# Battery_Charger.net
KiCad netlist of a schematic drawn in Altium Designer
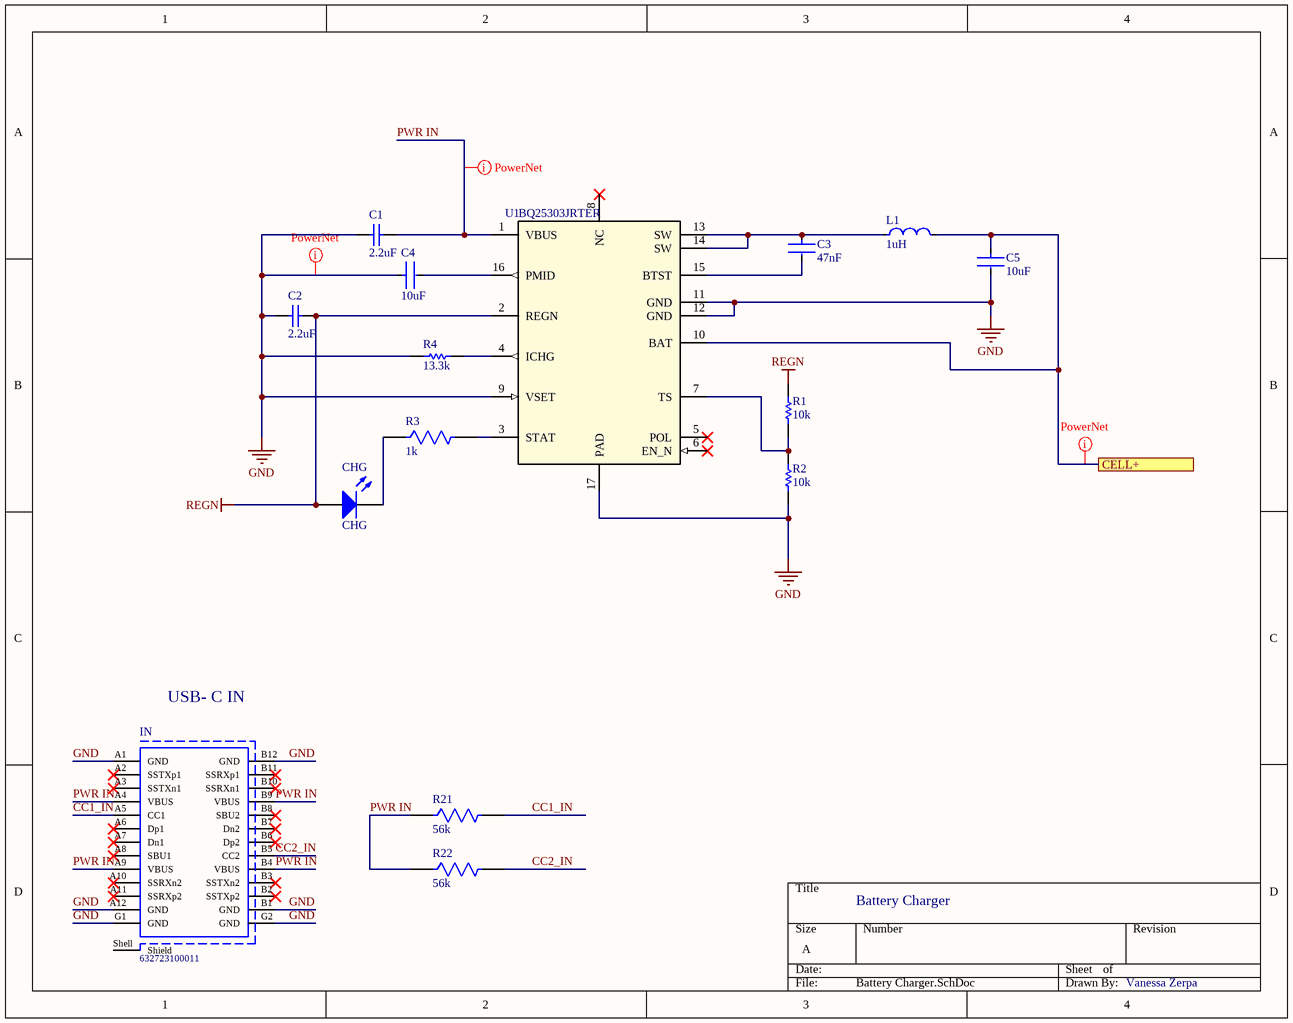
[diagram p0: Battery Charger.SchDoc]

(export (version "E")
  (design (tool "Eeschema 10.0.6"))
  (components
    (comp (ref "C1")
      (value "2.2uF")
      (footprint "CAPC2013X152X50ML20T25")
      (fields
        (field (name "PART NUMBER") "08053C225KAT2A")
        (field (name "MANUFACTURER") "AVX Interconnect / Elco")
      )
      (libsource (lib "Altium Content Vault") (part "CAP"))
    )
    (comp (ref "C2")
      (value "2.2uF")
      (footprint "CAPC2013X152X50ML20T25")
      (fields
        (field (name "PART NUMBER") "08053C225KAT2A")
        (field (name "MANUFACTURER") "AVX Interconnect / Elco")
      )
      (libsource (lib "Altium Content Vault") (part "CAP"))
    )
    (comp (ref "C3")
      (value "47nF")
      (footprint "FP-C0805C-DN-MFG")
      (description "CAP CER 0.047UF 25V 5% NP0 0805")
      (fields
        (field (name "MANUFACTURER PART NUMBER") "C0805C473J3GACTU")
        (field (name "OCTOPART") "https://octopart.com/c0805c473j3gactu-kemet-9563153")
      )
      (libsource (lib "Altium Content Vault") (part "b4654b650e69147ec39a6b967a45e02"))
    )
    (comp (ref "C4")
      (value "10uF")
      (footprint "FP-C0805C-DG-MFG")
      (description "CAP CER 10UF 10V X5R 0805")
      (fields (field (name "TOLERANCE") "10%") (field (name "MANUFACTURER PART NUMBER") "C0805C106K8PACTU"))
      (libsource (lib "Altium Content Vault") (part "11868f565c42a9108669ba33697ecf6"))
    )
    (comp (ref "C5")
      (value "10uF")
      (footprint "FP-C0805C-DG-MFG")
      (description "CAP CER 10UF 10V X5R 0805")
      (fields (field (name "TOLERANCE") "10%") (field (name "MANUFACTURER PART NUMBER") "C0805C106K8PACTU"))
      (libsource (lib "Altium Content Vault") (part "11868f565c42a9108669ba33697ecf6"))
    )
    (comp (ref "CHG")
      (value "CHG")
      (footprint "0805_A")
      (description "SMD mono-color Chip LED, WL-SMCW, Red")
      (fields (field (name "PARTNUMBER") "150080RS75000") (field (name "MANUFACTURER") "Wuerth Elektronik"))
      (libsource (lib "Altium Content Vault") (part "WE-LED_K1A2-2"))
    )
    (comp (ref "IN")
      (value "632723100011")
      (footprint "632723100011")
      (description "USB 3.1 Type C Receptacle WR-COM, Horizontal, SMT / THT")
      (fields (field (name "MANUFACTURER") "Wurth Elektronik") (field (name "PUBLISHER") "WurthElektronik"))
      (libsource (lib "Altium Content Vault") (part "WE-632723X00011"))
    )
    (comp (ref "L1")
      (value "1uH")
      (footprint "FP-LQM21DN_00-MFG")
      (description "Multilayer Type Inductor for General Circuits, 0805 (2012), 1μH, 10%, 0.4Ω, 50mA")
      (fields (field (name "TOLERANCE") "10%"))
      (libsource (lib "Altium Content Vault") (part "725321dda6339637d4d059423bc1c3c"))
    )
    (comp (ref "R1")
      (value "10k")
      (footprint "RESC2013X60X35NL10T20")
      (description "Chip Resistor, 10 KOhm, +/- 1%, 0.125 W, -55 to 155 degC, 0805 (2012 Metric), RoHS, Tape and Reel")
      (fields (field (name "MANUFACTURER") "Yageo"))
      (libsource (lib "Altium Content Vault") (part "RES-2"))
    )
    (comp (ref "R2")
      (value "10k")
      (footprint "RESC2013X60X35NL10T20")
      (description "Chip Resistor, 10 KOhm, +/- 1%, 0.125 W, -55 to 155 degC, 0805 (2012 Metric), RoHS, Tape and Reel")
      (fields (field (name "MANUFACTURER") "Yageo"))
      (libsource (lib "Altium Content Vault") (part "RES-2"))
    )
    (comp (ref "R3")
      (value "1k")
      (footprint "FP-CRCW0805-HPe3-IPC_A")
      (description "RES Thick Film, 1kΩ, 1%, 0.5W, 100ppm/°C, 0805")
      (fields (field (name "TOLERANCE") "1%"))
      (libsource (lib "Altium Content Vault") (part "1029c3af85768c4190bb7ad29bc67b5"))
    )
    (comp (ref "R4")
      (value "13.3k")
      (footprint "RESC2013X70X40LL20T20")
      (fields (field (name "MANUFACTURER") "Panasonic") (field (name "PART NUMBER") "ERJ-6ENF1332V"))
      (libsource (lib "Altium Content Vault") (part "RES"))
    )
    (comp (ref "R21")
      (value "56k")
      (footprint "FP-CRCW0805-e3-IPC_B")
      (description "RES Thick Film, 56kΩ, 1%, 0.125W, 100ppm/°C, 0805")
      (fields (field (name "TOLERANCE") "1%"))
      (libsource (lib "Altium Content Vault") (part "1029c3af85768c4190bb7ad29bc67b5"))
    )
    (comp (ref "R22")
      (value "56k")
      (footprint "FP-CRCW0805-e3-IPC_B")
      (description "RES Thick Film, 56kΩ, 1%, 0.125W, 100ppm/°C, 0805")
      (fields (field (name "TOLERANCE") "1%"))
      (libsource (lib "Altium Content Vault") (part "1029c3af85768c4190bb7ad29bc67b5"))
    )
    (comp (ref "U1")
      (value "BQ25303JRTER")
      (footprint "RTE0016C")
      (fields
        (field (name "MANUFACTURER") "Texas Instruments")
        (field (name "COPYRIGHT") "Copyright (C) 2021 Ultra Librarian. All rights reserved.")
      )
      (libsource (lib "BatteryCharger") (part "BQ25303JRTER"))
    )
  )
  (nets
    (net (code "1") (name "/CC1_IN") (class "Default")
      (node (ref "IN") (pin "A5") (pinfunction "CC1_A5") (pintype "passive"))
      (node (ref "R21") (pin "2") (pinfunction "2_2") (pintype "passive"))
    )
    (net (code "2") (name "/CC2_IN") (class "Default")
      (node (ref "IN") (pin "B5") (pinfunction "CC2_B5") (pintype "passive"))
      (node (ref "R22") (pin "2") (pinfunction "2_2") (pintype "passive"))
    )
    (net (code "3") (name "/CELL+") (class "Default")
      (node (ref "C5") (pin "1") (pinfunction "1_1") (pintype "passive"))
      (node (ref "L1") (pin "2") (pinfunction "2_2") (pintype "passive"))
      (node (ref "U1") (pin "10") (pinfunction "BAT_10") (pintype "power_in"))
    )
    (net (code "4") (name "/PWR IN") (class "Default")
      (node (ref "C1") (pin "2") (pinfunction "2_2") (pintype "passive"))
      (node (ref "IN") (pin "A4") (pinfunction "VBUS_A4") (pintype "passive"))
      (node (ref "IN") (pin "A9") (pinfunction "VBUS_A9") (pintype "passive"))
      (node (ref "IN") (pin "B4") (pinfunction "VBUS_B4") (pintype "passive"))
      (node (ref "IN") (pin "B9") (pinfunction "VBUS_B9") (pintype "passive"))
      (node (ref "R21") (pin "1") (pinfunction "1_1") (pintype "passive"))
      (node (ref "R22") (pin "1") (pinfunction "1_1") (pintype "passive"))
      (node (ref "U1") (pin "1") (pinfunction "VBUS_1") (pintype "power_in"))
    )
    (net (code "5") (name "GND") (class "Default")
      (node (ref "C1") (pin "1") (pinfunction "1_1") (pintype "passive"))
      (node (ref "C2") (pin "1") (pinfunction "1_1") (pintype "passive"))
      (node (ref "C4") (pin "1") (pinfunction "1_1") (pintype "passive"))
      (node (ref "C5") (pin "2") (pinfunction "2_2") (pintype "passive"))
      (node (ref "IN") (pin "A1") (pinfunction "GND_A1") (pintype "passive"))
      (node (ref "IN") (pin "A12") (pinfunction "GND_A12") (pintype "passive"))
      (node (ref "IN") (pin "B1") (pinfunction "GND_B1") (pintype "passive"))
      (node (ref "IN") (pin "B12") (pinfunction "GND_B12") (pintype "passive"))
      (node (ref "IN") (pin "G1") (pinfunction "GND_G1") (pintype "passive"))
      (node (ref "IN") (pin "G2") (pinfunction "GND_G2") (pintype "passive"))
      (node (ref "R2") (pin "1") (pinfunction "1_1") (pintype "passive"))
      (node (ref "R4") (pin "1") (pinfunction "1_1") (pintype "passive"))
      (node (ref "U1") (pin "11") (pinfunction "GND_11") (pintype "power_in"))
      (node (ref "U1") (pin "12") (pinfunction "GND_12") (pintype "power_in"))
      (node (ref "U1") (pin "17") (pinfunction "PAD_17") (pintype "power_in"))
      (node (ref "U1") (pin "9") (pinfunction "VSET_9") (pintype "input"))
    )
    (net (code "6") (name "Net-(C3-Pad1)") (class "Default")
      (node (ref "C3") (pin "1") (pinfunction "1_1") (pintype "passive"))
      (node (ref "L1") (pin "1") (pinfunction "1_1") (pintype "passive"))
      (node (ref "U1") (pin "13") (pinfunction "SW_13") (pintype "power_in"))
      (node (ref "U1") (pin "14") (pinfunction "SW_14") (pintype "power_in"))
    )
    (net (code "7") (name "Net-(CHG-K)") (class "Default")
      (node (ref "CHG") (pin "1") (pinfunction "K_1") (pintype "passive"))
      (node (ref "R3") (pin "1") (pinfunction "1_1") (pintype "passive"))
    )
    (net (code "8") (name "Net-(U1-BTST)") (class "Default")
      (node (ref "C3") (pin "2") (pinfunction "2_2") (pintype "passive"))
      (node (ref "U1") (pin "15") (pinfunction "BTST_15") (pintype "power_in"))
    )
    (net (code "9") (name "Net-(U1-ICHG)") (class "Default")
      (node (ref "R4") (pin "2") (pinfunction "2_2") (pintype "passive"))
      (node (ref "U1") (pin "4") (pinfunction "ICHG_4") (pintype "output"))
    )
    (net (code "10") (name "Net-(U1-PMID)") (class "Default")
      (node (ref "C4") (pin "2") (pinfunction "2_2") (pintype "passive"))
      (node (ref "U1") (pin "16") (pinfunction "PMID_16") (pintype "output"))
    )
    (net (code "11") (name "Net-(U1-STAT)") (class "Default")
      (node (ref "R3") (pin "2") (pinfunction "2_2") (pintype "passive"))
      (node (ref "U1") (pin "3") (pinfunction "STAT_3") (pintype "open_collector"))
    )
    (net (code "12") (name "Net-(U1-TS)") (class "Default")
      (node (ref "R1") (pin "1") (pinfunction "1_1") (pintype "passive"))
      (node (ref "R2") (pin "2") (pinfunction "2_2") (pintype "passive"))
      (node (ref "U1") (pin "7") (pinfunction "TS_7") (pintype "passive"))
    )
    (net (code "13") (name "REGN") (class "Default")
      (node (ref "C2") (pin "2") (pinfunction "2_2") (pintype "passive"))
      (node (ref "CHG") (pin "2") (pinfunction "A_2") (pintype "passive"))
      (node (ref "R1") (pin "2") (pinfunction "2_2") (pintype "passive"))
      (node (ref "U1") (pin "2") (pinfunction "REGN_2") (pintype "power_in"))
    )
    (net (code "14") (name "unconnected-(IN-Dn1-PadA7)") (class "Default")
      (node (ref "IN") (pin "A7") (pinfunction "Dn1_A7") (pintype "passive+no_connect"))
    )
    (net (code "15") (name "unconnected-(IN-Dn2-PadB7)") (class "Default")
      (node (ref "IN") (pin "B7") (pinfunction "Dn2_B7") (pintype "passive+no_connect"))
    )
    (net (code "16") (name "unconnected-(IN-Dp1-PadA6)") (class "Default")
      (node (ref "IN") (pin "A6") (pinfunction "Dp1_A6") (pintype "passive+no_connect"))
    )
    (net (code "17") (name "unconnected-(IN-Dp2-PadB6)") (class "Default")
      (node (ref "IN") (pin "B6") (pinfunction "Dp2_B6") (pintype "passive+no_connect"))
    )
    (net (code "18") (name "unconnected-(IN-SBU1-PadA8)") (class "Default")
      (node (ref "IN") (pin "A8") (pinfunction "SBU1_A8") (pintype "passive+no_connect"))
    )
    (net (code "19") (name "unconnected-(IN-SBU2-PadB8)") (class "Default")
      (node (ref "IN") (pin "B8") (pinfunction "SBU2_B8") (pintype "passive+no_connect"))
    )
    (net (code "20") (name "unconnected-(IN-SSRXn1-PadB10)") (class "Default")
      (node (ref "IN") (pin "B10") (pinfunction "SSRXn1_B10") (pintype "passive+no_connect"))
    )
    (net (code "21") (name "unconnected-(IN-SSRXn2-PadA10)") (class "Default")
      (node (ref "IN") (pin "A10") (pinfunction "SSRXn2_A10") (pintype "passive+no_connect"))
    )
    (net (code "22") (name "unconnected-(IN-SSRXp1-PadB11)") (class "Default")
      (node (ref "IN") (pin "B11") (pinfunction "SSRXp1_B11") (pintype "passive+no_connect"))
    )
    (net (code "23") (name "unconnected-(IN-SSRXp2-PadA11)") (class "Default")
      (node (ref "IN") (pin "A11") (pinfunction "SSRXp2_A11") (pintype "passive+no_connect"))
    )
    (net (code "24") (name "unconnected-(IN-SSTXn1-PadA3)") (class "Default")
      (node (ref "IN") (pin "A3") (pinfunction "SSTXn1_A3") (pintype "passive+no_connect"))
    )
    (net (code "25") (name "unconnected-(IN-SSTXn2-PadB3)") (class "Default")
      (node (ref "IN") (pin "B3") (pinfunction "SSTXn2_B3") (pintype "passive+no_connect"))
    )
    (net (code "26") (name "unconnected-(IN-SSTXp1-PadA2)") (class "Default")
      (node (ref "IN") (pin "A2") (pinfunction "SSTXp1_A2") (pintype "passive+no_connect"))
    )
    (net (code "27") (name "unconnected-(IN-SSTXp2-PadB2)") (class "Default")
      (node (ref "IN") (pin "B2") (pinfunction "SSTXp2_B2") (pintype "passive+no_connect"))
    )
    (net (code "28") (name "unconnected-(IN-Shield-PadShell)") (class "Default")
      (node (ref "IN") (pin "Shell") (pinfunction "Shield_Shell") (pintype "passive"))
    )
    (net (code "29") (name "unconnected-(U1-EN_N-Pad6)") (class "Default")
      (node (ref "U1") (pin "6") (pinfunction "EN_N_6") (pintype "input+no_connect"))
    )
    (net (code "30") (name "unconnected-(U1-NC-Pad8)") (class "Default")
      (node (ref "U1") (pin "8") (pinfunction "NC_8") (pintype "passive+no_connect"))
    )
    (net (code "31") (name "unconnected-(U1-POL-Pad5)") (class "Default")
      (node (ref "U1") (pin "5") (pinfunction "POL_5") (pintype "passive+no_connect"))
    )
  )
)
